# I2C-Keypad-Backpack.net
KiCad netlist of a schematic drawn in EAGLE
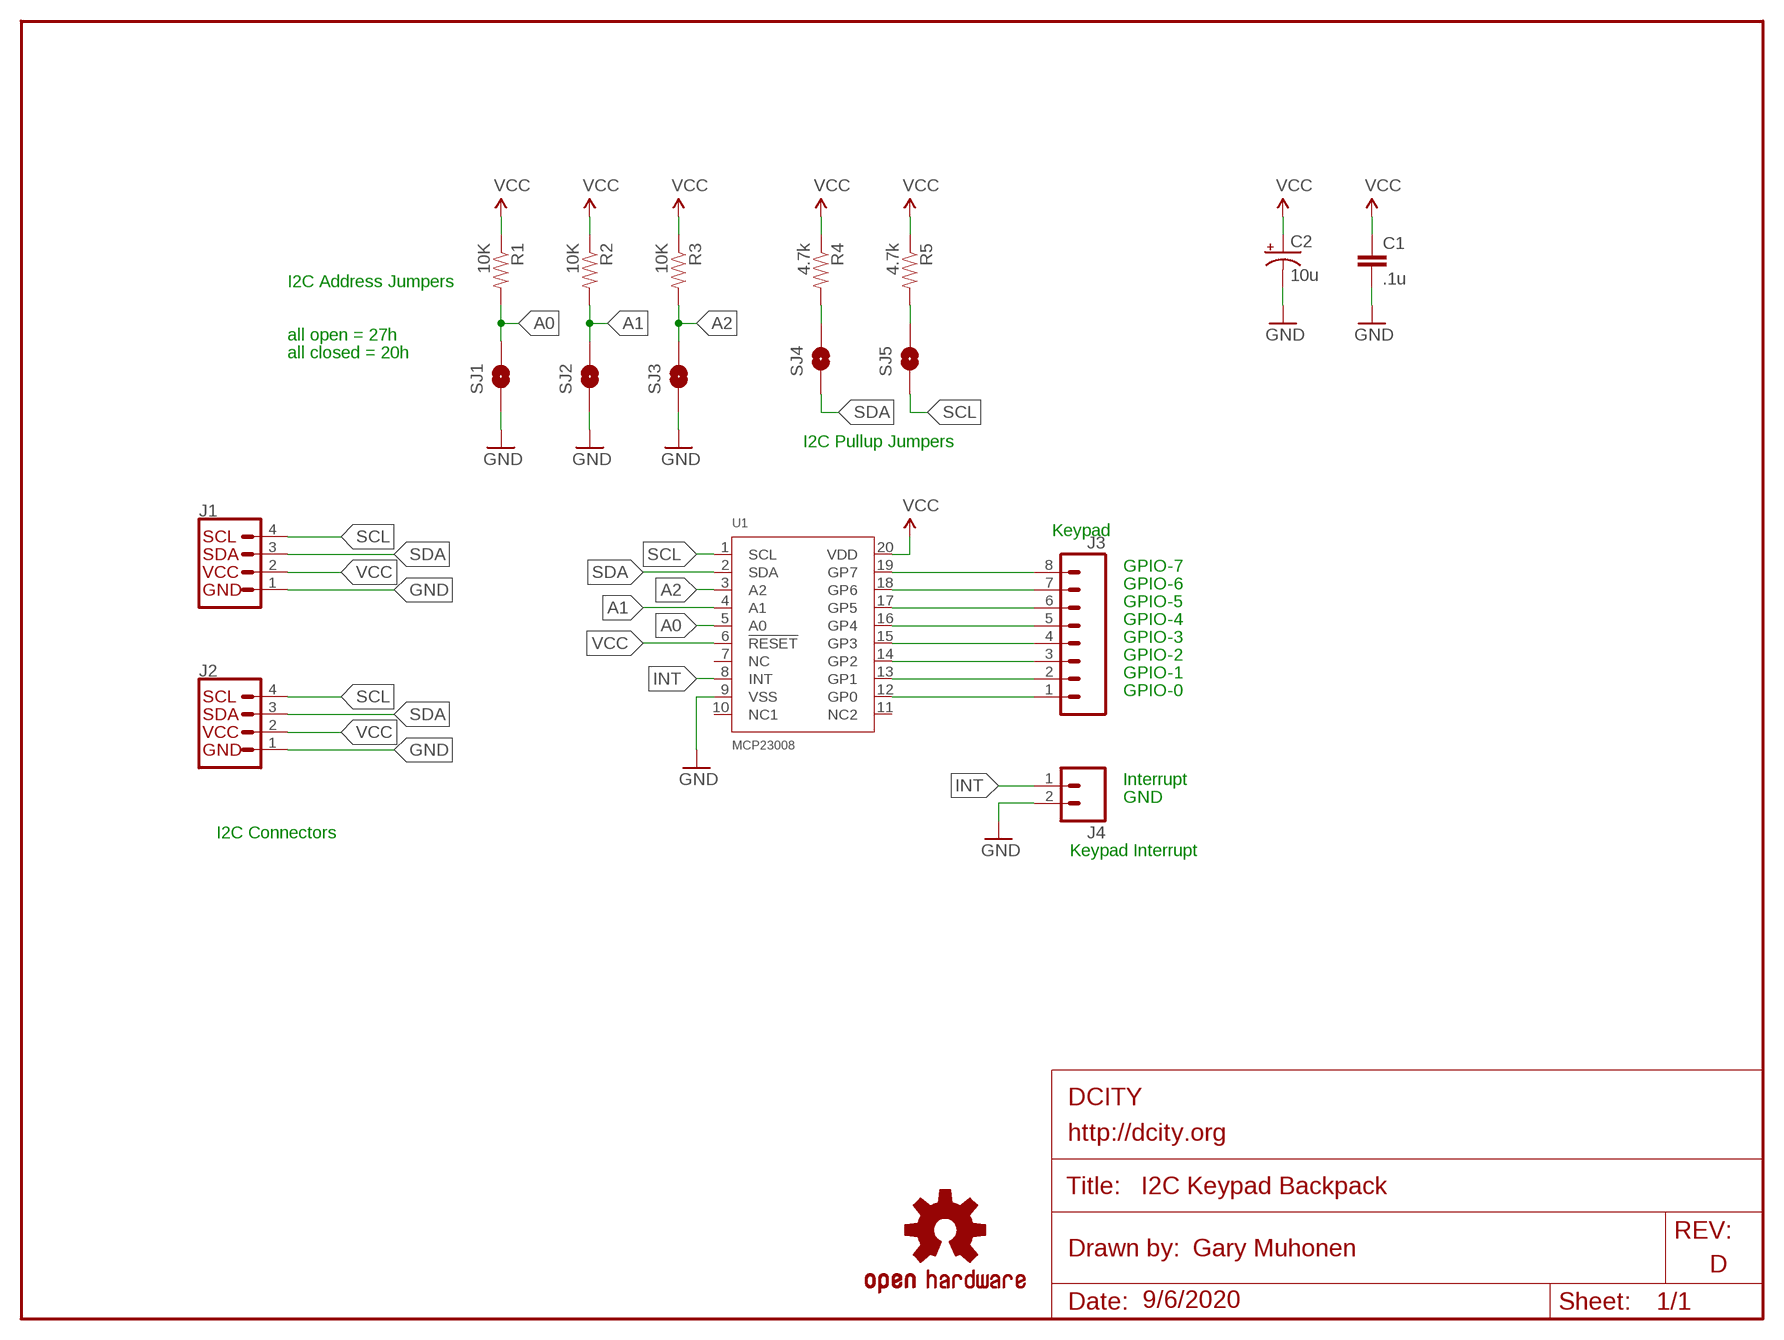
[diagram p0: schematic, sheet 1]

(export (version "E")
  (design (tool "Eeschema 10.0.6"))
  (components
    (comp (ref "C1")
      (value ".1u")
      (footprint "eagle-import:0805-CAP")
      (libsource (lib "eagle-import") (part "CAP0805"))
    )
    (comp (ref "C2")
      (value "10u")
      (footprint "eagle-import:0805-POL")
      (libsource (lib "eagle-import") (part "CAP_POL0805"))
    )
    (comp (ref "J1")
      (value "QWIIC_RIGHT_ANGLE")
      (footprint "eagle-import:JST04_1MM_RA")
      (libsource (lib "eagle-import") (part "QWIIC_CONNECTORJS-1MM"))
    )
    (comp (ref "J2")
      (value "QWIIC_RIGHT_ANGLE")
      (footprint "eagle-import:JST04_1MM_RA")
      (libsource (lib "eagle-import") (part "QWIIC_CONNECTORJS-1MM"))
    )
    (comp (ref "J3")
      (value "M08LOCK")
      (footprint "eagle-import:1X08_LOCK")
      (libsource (lib "eagle-import") (part "M08LOCK"))
    )
    (comp (ref "J4")
      (value "M02LOCK")
      (footprint "eagle-import:1X02_LOCK")
      (libsource (lib "eagle-import") (part "M02LOCK"))
    )
    (comp (ref "LOGO1")
      (value "OSHW-LOGOS")
      (footprint "eagle-import:OSHW-LOGO-S")
      (libsource (lib "eagle-import") (part "OSHW-LOGOS"))
    )
    (comp (ref "R1")
      (value "10K")
      (footprint "eagle-import:0805-RES")
      (libsource (lib "eagle-import") (part "RESISTOR0805"))
    )
    (comp (ref "R2")
      (value "10K")
      (footprint "eagle-import:0805-RES")
      (libsource (lib "eagle-import") (part "RESISTOR0805"))
    )
    (comp (ref "R3")
      (value "10K")
      (footprint "eagle-import:0805-RES")
      (libsource (lib "eagle-import") (part "RESISTOR0805"))
    )
    (comp (ref "R4")
      (value "4.7k")
      (footprint "eagle-import:0805-RES")
      (libsource (lib "eagle-import") (part "RESISTOR0805"))
    )
    (comp (ref "R5")
      (value "4.7k")
      (footprint "eagle-import:0805-RES")
      (libsource (lib "eagle-import") (part "RESISTOR0805"))
    )
    (comp (ref "SJ1")
      (value "SOLDERJUMPERNC")
      (footprint "eagle-import:SJ_2S")
      (libsource (lib "eagle-import") (part "SOLDERJUMPERNC"))
    )
    (comp (ref "SJ2")
      (value "SOLDERJUMPERNC")
      (footprint "eagle-import:SJ_2S")
      (libsource (lib "eagle-import") (part "SOLDERJUMPERNC"))
    )
    (comp (ref "SJ3")
      (value "SOLDERJUMPERNC")
      (footprint "eagle-import:SJ_2S")
      (libsource (lib "eagle-import") (part "SOLDERJUMPERNC"))
    )
    (comp (ref "SJ4")
      (value "SOLDERJUMPERNC")
      (footprint "eagle-import:SJ_2S")
      (libsource (lib "eagle-import") (part "SOLDERJUMPERNC"))
    )
    (comp (ref "SJ5")
      (value "SOLDERJUMPERNC")
      (footprint "eagle-import:SJ_2S")
      (libsource (lib "eagle-import") (part "SOLDERJUMPERNC"))
    )
    (comp (ref "U1")
      (value "MCP23008")
      (footprint "eagle-import:SSOP20-0.65-7.6X5.2MM")
      (libsource (lib "eagle-import") (part "MCP23008-E/SS"))
    )
  )
  (nets
    (net (code "1") (name "A0") (class "Default")
      (node (ref "R1") (pin "2") (pinfunction "2_2") (pintype "passive"))
      (node (ref "SJ1") (pin "2") (pinfunction "2_2") (pintype "passive"))
      (node (ref "U1") (pin "5") (pinfunction "A0_5") (pintype "bidirectional"))
    )
    (net (code "2") (name "A1") (class "Default")
      (node (ref "R2") (pin "2") (pinfunction "2_2") (pintype "passive"))
      (node (ref "SJ2") (pin "2") (pinfunction "2_2") (pintype "passive"))
      (node (ref "U1") (pin "4") (pinfunction "A1_4") (pintype "bidirectional"))
    )
    (net (code "3") (name "A2") (class "Default")
      (node (ref "R3") (pin "2") (pinfunction "2_2") (pintype "passive"))
      (node (ref "SJ3") (pin "2") (pinfunction "2_2") (pintype "passive"))
      (node (ref "U1") (pin "3") (pinfunction "A2_3") (pintype "bidirectional"))
    )
    (net (code "4") (name "GND") (class "Default")
      (node (ref "C1") (pin "2") (pinfunction "2_2") (pintype "passive"))
      (node (ref "C2") (pin "-") (pinfunction "-_-") (pintype "passive"))
      (node (ref "J1") (pin "1") (pinfunction "1_1") (pintype "power_in"))
      (node (ref "J2") (pin "1") (pinfunction "1_1") (pintype "power_in"))
      (node (ref "J4") (pin "2") (pinfunction "2_2") (pintype "passive"))
      (node (ref "SJ1") (pin "1") (pinfunction "1_1") (pintype "passive"))
      (node (ref "SJ2") (pin "1") (pinfunction "1_1") (pintype "passive"))
      (node (ref "SJ3") (pin "1") (pinfunction "1_1") (pintype "passive"))
      (node (ref "U1") (pin "9") (pinfunction "VSS_9") (pintype "bidirectional"))
    )
    (net (code "5") (name "INT") (class "Default")
      (node (ref "J4") (pin "1") (pinfunction "1_1") (pintype "passive"))
      (node (ref "U1") (pin "8") (pinfunction "INT_8") (pintype "bidirectional"))
    )
    (net (code "6") (name "Net-(R4-Pad2)") (class "Default")
      (node (ref "R4") (pin "2") (pinfunction "2_2") (pintype "passive"))
      (node (ref "SJ4") (pin "2") (pinfunction "2_2") (pintype "passive"))
    )
    (net (code "7") (name "Net-(R5-Pad2)") (class "Default")
      (node (ref "R5") (pin "2") (pinfunction "2_2") (pintype "passive"))
      (node (ref "SJ5") (pin "2") (pinfunction "2_2") (pintype "passive"))
    )
    (net (code "8") (name "Net-(U1-GP0)") (class "Default")
      (node (ref "J3") (pin "1") (pinfunction "1_1") (pintype "passive"))
      (node (ref "U1") (pin "12") (pinfunction "GP0_12") (pintype "bidirectional"))
    )
    (net (code "9") (name "Net-(U1-GP1)") (class "Default")
      (node (ref "J3") (pin "2") (pinfunction "2_2") (pintype "passive"))
      (node (ref "U1") (pin "13") (pinfunction "GP1_13") (pintype "bidirectional"))
    )
    (net (code "10") (name "Net-(U1-GP2)") (class "Default")
      (node (ref "J3") (pin "3") (pinfunction "3_3") (pintype "passive"))
      (node (ref "U1") (pin "14") (pinfunction "GP2_14") (pintype "bidirectional"))
    )
    (net (code "11") (name "Net-(U1-GP3)") (class "Default")
      (node (ref "J3") (pin "4") (pinfunction "4_4") (pintype "passive"))
      (node (ref "U1") (pin "15") (pinfunction "GP3_15") (pintype "bidirectional"))
    )
    (net (code "12") (name "Net-(U1-GP4)") (class "Default")
      (node (ref "J3") (pin "5") (pinfunction "5_5") (pintype "passive"))
      (node (ref "U1") (pin "16") (pinfunction "GP4_16") (pintype "bidirectional"))
    )
    (net (code "13") (name "Net-(U1-GP5)") (class "Default")
      (node (ref "J3") (pin "6") (pinfunction "6_6") (pintype "passive"))
      (node (ref "U1") (pin "17") (pinfunction "GP5_17") (pintype "bidirectional"))
    )
    (net (code "14") (name "Net-(U1-GP6)") (class "Default")
      (node (ref "J3") (pin "7") (pinfunction "7_7") (pintype "passive"))
      (node (ref "U1") (pin "18") (pinfunction "GP6_18") (pintype "bidirectional"))
    )
    (net (code "15") (name "Net-(U1-GP7)") (class "Default")
      (node (ref "J3") (pin "8") (pinfunction "8_8") (pintype "passive"))
      (node (ref "U1") (pin "19") (pinfunction "GP7_19") (pintype "bidirectional"))
    )
    (net (code "16") (name "SCL") (class "Default")
      (node (ref "J1") (pin "4") (pinfunction "4_4") (pintype "passive"))
      (node (ref "J2") (pin "4") (pinfunction "4_4") (pintype "passive"))
      (node (ref "SJ5") (pin "1") (pinfunction "1_1") (pintype "passive"))
      (node (ref "U1") (pin "1") (pinfunction "SCL_1") (pintype "bidirectional"))
    )
    (net (code "17") (name "SDA") (class "Default")
      (node (ref "J1") (pin "3") (pinfunction "3_3") (pintype "passive"))
      (node (ref "J2") (pin "3") (pinfunction "3_3") (pintype "passive"))
      (node (ref "SJ4") (pin "1") (pinfunction "1_1") (pintype "passive"))
      (node (ref "U1") (pin "2") (pinfunction "SDA_2") (pintype "bidirectional"))
    )
    (net (code "18") (name "VCC") (class "Default")
      (node (ref "C1") (pin "1") (pinfunction "1_1") (pintype "passive"))
      (node (ref "C2") (pin "+") (pinfunction "+_+") (pintype "passive"))
      (node (ref "J1") (pin "2") (pinfunction "2_2") (pintype "power_in"))
      (node (ref "J2") (pin "2") (pinfunction "2_2") (pintype "power_in"))
      (node (ref "R1") (pin "1") (pinfunction "1_1") (pintype "passive"))
      (node (ref "R2") (pin "1") (pinfunction "1_1") (pintype "passive"))
      (node (ref "R3") (pin "1") (pinfunction "1_1") (pintype "passive"))
      (node (ref "R4") (pin "1") (pinfunction "1_1") (pintype "passive"))
      (node (ref "R5") (pin "1") (pinfunction "1_1") (pintype "passive"))
      (node (ref "U1") (pin "20") (pinfunction "VDD_20") (pintype "bidirectional"))
      (node (ref "U1") (pin "6") (pinfunction "~{RESET}_6") (pintype "bidirectional"))
    )
    (net (code "19") (name "unconnected-(U1-NC-Pad7)") (class "Default")
      (node (ref "U1") (pin "7") (pinfunction "NC_7") (pintype "bidirectional"))
    )
    (net (code "20") (name "unconnected-(U1-NC1-Pad10)") (class "Default")
      (node (ref "U1") (pin "10") (pinfunction "NC1_10") (pintype "bidirectional"))
    )
    (net (code "21") (name "unconnected-(U1-NC2-Pad11)") (class "Default")
      (node (ref "U1") (pin "11") (pinfunction "NC2_11") (pintype "bidirectional"))
    )
  )
)
